# 153-06A_Mode_X_with_status_LEDs.net
KiCad netlist of a schematic drawn in EAGLE
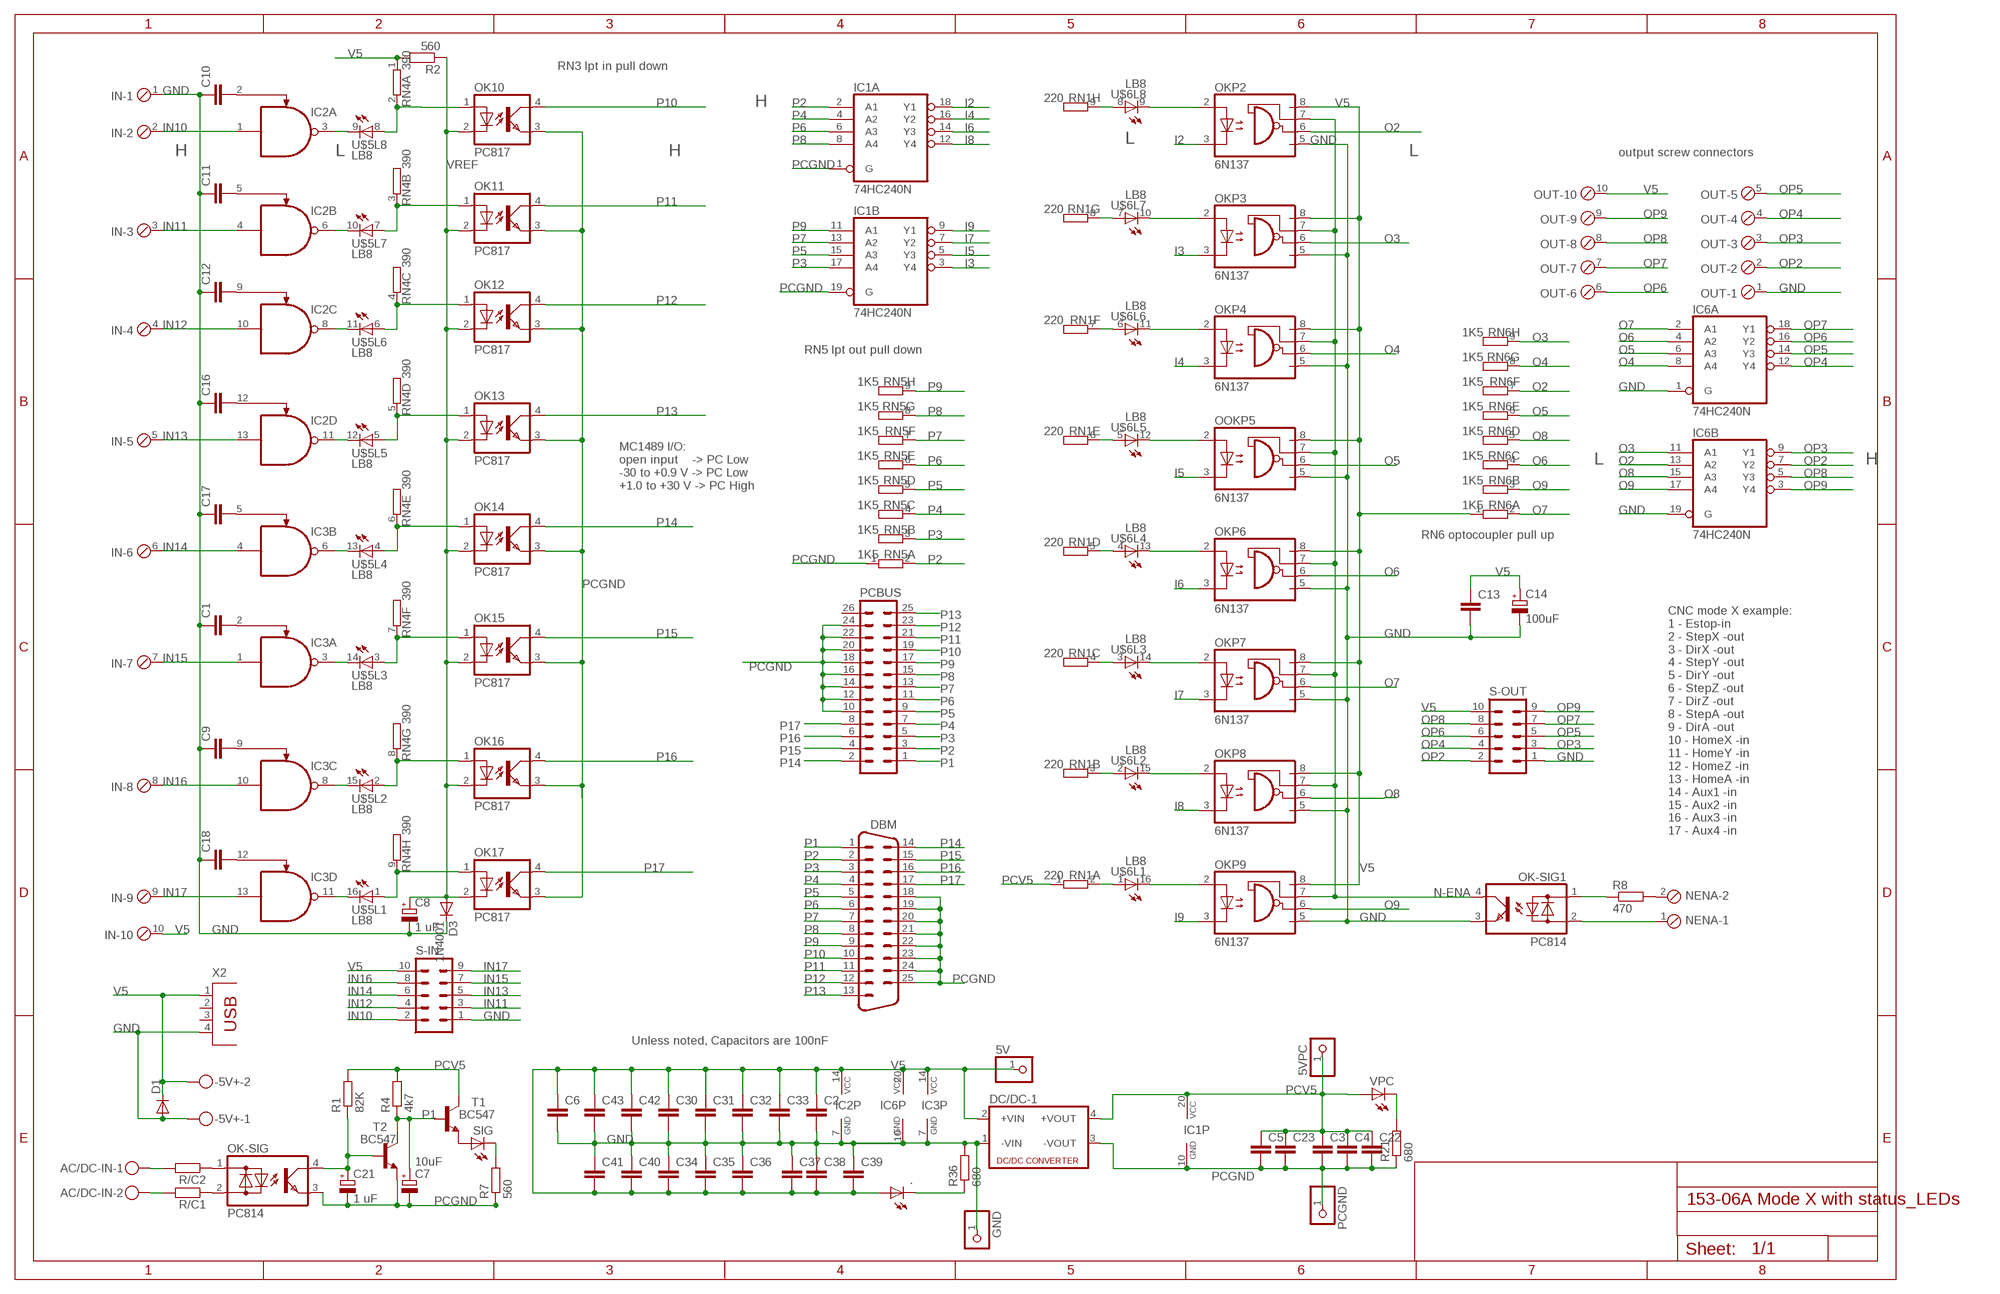
[diagram p0: schematic, sheet 1]

(export (version "E")
  (design (tool "Eeschema 10.0.6"))
  (components
    (comp (ref "-5V+")
      (value "MKDSN1,5/2-5,08")
      (footprint "eagle-import:MKDSN1,5_2-5,08")
      (libsource (lib "eagle-import") (part "MKDSN1,5/2-5,08"))
    )
    (comp (ref ".")
      (value "LED3MM")
      (footprint "eagle-import:LED3MM")
      (libsource (lib "eagle-import") (part "LED3MM"))
    )
    (comp (ref "5V")
      (value "PINHD-1X1")
      (footprint "eagle-import:1X01")
      (libsource (lib "eagle-import") (part "PINHD-1X1"))
    )
    (comp (ref "5VPC")
      (value "PINHD-1X1")
      (footprint "eagle-import:1X01")
      (libsource (lib "eagle-import") (part "PINHD-1X1"))
    )
    (comp (ref "AC/DC-IN")
      (value "MKDSN1,5/2-5,08")
      (footprint "eagle-import:MKDSN1,5_2-5,08")
      (libsource (lib "eagle-import") (part "MKDSN1,5/2-5,08"))
    )
    (comp (ref "C1")
      (value "C-EU025-024X044")
      (footprint "eagle-import:C025-024X044")
      (libsource (lib "eagle-import") (part "C-EU025-024X044"))
    )
    (comp (ref "C2")
      (value "C-EU025-024X044")
      (footprint "eagle-import:C025-024X044")
      (libsource (lib "eagle-import") (part "C-EU025-024X044"))
    )
    (comp (ref "C3")
      (value "C-EU025-024X044")
      (footprint "eagle-import:C025-024X044")
      (libsource (lib "eagle-import") (part "C-EU025-024X044"))
    )
    (comp (ref "C4")
      (value "C-EU025-024X044")
      (footprint "eagle-import:C025-024X044")
      (libsource (lib "eagle-import") (part "C-EU025-024X044"))
    )
    (comp (ref "C5")
      (value "C-EU025-024X044")
      (footprint "eagle-import:C025-024X044")
      (libsource (lib "eagle-import") (part "C-EU025-024X044"))
    )
    (comp (ref "C6")
      (value "C-EU025-024X044")
      (footprint "eagle-import:C025-024X044")
      (libsource (lib "eagle-import") (part "C-EU025-024X044"))
    )
    (comp (ref "C7")
      (value "10uF")
      (footprint "eagle-import:E5-6")
      (libsource (lib "eagle-import") (part "CPOL-EUE5-6"))
    )
    (comp (ref "C8")
      (value "1 uF")
      (footprint "eagle-import:E2,5-6")
      (libsource (lib "eagle-import") (part "CPOL-EUE2.5-6"))
    )
    (comp (ref "C9")
      (value "C-EU025-024X044")
      (footprint "eagle-import:C025-024X044")
      (libsource (lib "eagle-import") (part "C-EU025-024X044"))
    )
    (comp (ref "C10")
      (value "C-EU025-024X044")
      (footprint "eagle-import:C025-024X044")
      (libsource (lib "eagle-import") (part "C-EU025-024X044"))
    )
    (comp (ref "C11")
      (value "C-EU025-024X044")
      (footprint "eagle-import:C025-024X044")
      (libsource (lib "eagle-import") (part "C-EU025-024X044"))
    )
    (comp (ref "C12")
      (value "C-EU025-024X044")
      (footprint "eagle-import:C025-024X044")
      (libsource (lib "eagle-import") (part "C-EU025-024X044"))
    )
    (comp (ref "C13")
      (value "C-EU025-024X044")
      (footprint "eagle-import:C025-024X044")
      (libsource (lib "eagle-import") (part "C-EU025-024X044"))
    )
    (comp (ref "C14")
      (value "100uF")
      (footprint "eagle-import:E3,5-8")
      (libsource (lib "eagle-import") (part "CPOL-EUE3.5-8"))
    )
    (comp (ref "C16")
      (value "C-EU025-024X044")
      (footprint "eagle-import:C025-024X044")
      (libsource (lib "eagle-import") (part "C-EU025-024X044"))
    )
    (comp (ref "C17")
      (value "C-EU025-024X044")
      (footprint "eagle-import:C025-024X044")
      (libsource (lib "eagle-import") (part "C-EU025-024X044"))
    )
    (comp (ref "C18")
      (value "C-EU025-024X044")
      (footprint "eagle-import:C025-024X044")
      (libsource (lib "eagle-import") (part "C-EU025-024X044"))
    )
    (comp (ref "C21")
      (value "1 uF")
      (footprint "eagle-import:E2,5-6")
      (libsource (lib "eagle-import") (part "CPOL-EUE2.5-6"))
    )
    (comp (ref "C22")
      (value "C-EU025-024X044")
      (footprint "eagle-import:C025-024X044")
      (libsource (lib "eagle-import") (part "C-EU025-024X044"))
    )
    (comp (ref "C23")
      (value "C-EU025-024X044")
      (footprint "eagle-import:C025-024X044")
      (libsource (lib "eagle-import") (part "C-EU025-024X044"))
    )
    (comp (ref "C30")
      (value "C-EU025-024X044")
      (footprint "eagle-import:C025-024X044")
      (libsource (lib "eagle-import") (part "C-EU025-024X044"))
    )
    (comp (ref "C31")
      (value "C-EU025-024X044")
      (footprint "eagle-import:C025-024X044")
      (libsource (lib "eagle-import") (part "C-EU025-024X044"))
    )
    (comp (ref "C32")
      (value "C-EU025-024X044")
      (footprint "eagle-import:C025-024X044")
      (libsource (lib "eagle-import") (part "C-EU025-024X044"))
    )
    (comp (ref "C33")
      (value "C-EU025-024X044")
      (footprint "eagle-import:C025-024X044")
      (libsource (lib "eagle-import") (part "C-EU025-024X044"))
    )
    (comp (ref "C34")
      (value "C-EU025-024X044")
      (footprint "eagle-import:C025-024X044")
      (libsource (lib "eagle-import") (part "C-EU025-024X044"))
    )
    (comp (ref "C35")
      (value "C-EU025-024X044")
      (footprint "eagle-import:C025-024X044")
      (libsource (lib "eagle-import") (part "C-EU025-024X044"))
    )
    (comp (ref "C36")
      (value "C-EU025-024X044")
      (footprint "eagle-import:C025-024X044")
      (libsource (lib "eagle-import") (part "C-EU025-024X044"))
    )
    (comp (ref "C37")
      (value "C-EU025-024X044")
      (footprint "eagle-import:C025-024X044")
      (libsource (lib "eagle-import") (part "C-EU025-024X044"))
    )
    (comp (ref "C38")
      (value "C-EU025-024X044")
      (footprint "eagle-import:C025-024X044")
      (libsource (lib "eagle-import") (part "C-EU025-024X044"))
    )
    (comp (ref "C39")
      (value "C-EU025-024X044")
      (footprint "eagle-import:C025-024X044")
      (libsource (lib "eagle-import") (part "C-EU025-024X044"))
    )
    (comp (ref "C40")
      (value "C-EU025-024X044")
      (footprint "eagle-import:C025-024X044")
      (libsource (lib "eagle-import") (part "C-EU025-024X044"))
    )
    (comp (ref "C41")
      (value "C-EU025-024X044")
      (footprint "eagle-import:C025-024X044")
      (libsource (lib "eagle-import") (part "C-EU025-024X044"))
    )
    (comp (ref "C42")
      (value "C-EU025-024X044")
      (footprint "eagle-import:C025-024X044")
      (libsource (lib "eagle-import") (part "C-EU025-024X044"))
    )
    (comp (ref "C43")
      (value "C-EU025-024X044")
      (footprint "eagle-import:C025-024X044")
      (libsource (lib "eagle-import") (part "C-EU025-024X044"))
    )
    (comp (ref "D1")
      (value "1N4148DO35-10")
      (footprint "eagle-import:DO35-10")
      (libsource (lib "eagle-import") (part "1N4148DO35-10"))
    )
    (comp (ref "D3")
      (value "1N4001")
      (footprint "eagle-import:DO35-10")
      (libsource (lib "eagle-import") (part "1N4148DO35-10"))
    )
    (comp (ref "DBM")
      (value "M25HP")
      (footprint "eagle-import:M25HP")
      (libsource (lib "eagle-import") (part "M25HP"))
    )
    (comp (ref "DC/DC-1")
      (value "VA-1205S")
      (footprint "eagle-import:4SIL")
      (libsource (lib "eagle-import") (part "VA-?S1205"))
    )
    (comp (ref "GND")
      (value "PINHD-1X1")
      (footprint "eagle-import:1X01")
      (libsource (lib "eagle-import") (part "PINHD-1X1"))
    )
    (comp (ref "IC1")
      (value "74HC240N")
      (footprint "eagle-import:DIL20")
      (libsource (lib "eagle-import") (part "74240NHC"))
    )
    (comp (ref "IC2")
      (value "MC1489DIP")
      (footprint "eagle-import:DIL14")
      (libsource (lib "eagle-import") (part "MC1489DIP"))
    )
    (comp (ref "IC3")
      (value "MC1489DIP")
      (footprint "eagle-import:DIL14")
      (libsource (lib "eagle-import") (part "MC1489DIP"))
    )
    (comp (ref "IC6")
      (value "74HC240N")
      (footprint "eagle-import:DIL20")
      (libsource (lib "eagle-import") (part "74240NHC"))
    )
    (comp (ref "IN")
      (value "MPT10")
      (footprint "eagle-import:10POL254")
      (libsource (lib "eagle-import") (part "MPT10"))
    )
    (comp (ref "NENA")
      (value "MPT2")
      (footprint "eagle-import:2POL254")
      (libsource (lib "eagle-import") (part "MPT2"))
    )
    (comp (ref "OK-SIG")
      (value "PC814")
      (footprint "eagle-import:DIL04")
      (libsource (lib "eagle-import") (part "PC814"))
    )
    (comp (ref "OK-SIG1")
      (value "PC814")
      (footprint "eagle-import:DIL04")
      (libsource (lib "eagle-import") (part "PC814"))
    )
    (comp (ref "OK10")
      (value "PC817")
      (footprint "eagle-import:DIL04")
      (fields (field (name "MPN") "PC817X4J000F"))
      (libsource (lib "eagle-import") (part "PC817"))
    )
    (comp (ref "OK11")
      (value "PC817")
      (footprint "eagle-import:DIL04")
      (fields (field (name "MPN") "PC817X4J000F"))
      (libsource (lib "eagle-import") (part "PC817"))
    )
    (comp (ref "OK12")
      (value "PC817")
      (footprint "eagle-import:DIL04")
      (fields (field (name "MPN") "PC817X4J000F"))
      (libsource (lib "eagle-import") (part "PC817"))
    )
    (comp (ref "OK13")
      (value "PC817")
      (footprint "eagle-import:DIL04")
      (fields (field (name "MPN") "PC817X4J000F"))
      (libsource (lib "eagle-import") (part "PC817"))
    )
    (comp (ref "OK14")
      (value "PC817")
      (footprint "eagle-import:DIL04")
      (fields (field (name "MPN") "PC817X4J000F"))
      (libsource (lib "eagle-import") (part "PC817"))
    )
    (comp (ref "OK15")
      (value "PC817")
      (footprint "eagle-import:DIL04")
      (fields (field (name "MPN") "PC817X4J000F"))
      (libsource (lib "eagle-import") (part "PC817"))
    )
    (comp (ref "OK16")
      (value "PC817")
      (footprint "eagle-import:DIL04")
      (fields (field (name "MPN") "PC817X4J000F"))
      (libsource (lib "eagle-import") (part "PC817"))
    )
    (comp (ref "OK17")
      (value "PC817")
      (footprint "eagle-import:DIL04")
      (fields (field (name "MPN") "PC817X4J000F"))
      (libsource (lib "eagle-import") (part "PC817"))
    )
    (comp (ref "OKP2")
      (value "6N137")
      (footprint "eagle-import:DIL08")
      (libsource (lib "eagle-import") (part "6N137"))
    )
    (comp (ref "OKP3")
      (value "6N137")
      (footprint "eagle-import:DIL08")
      (libsource (lib "eagle-import") (part "6N137"))
    )
    (comp (ref "OKP4")
      (value "6N137")
      (footprint "eagle-import:DIL08")
      (libsource (lib "eagle-import") (part "6N137"))
    )
    (comp (ref "OKP6")
      (value "6N137")
      (footprint "eagle-import:DIL08")
      (libsource (lib "eagle-import") (part "6N137"))
    )
    (comp (ref "OKP7")
      (value "6N137")
      (footprint "eagle-import:DIL08")
      (libsource (lib "eagle-import") (part "6N137"))
    )
    (comp (ref "OKP8")
      (value "6N137")
      (footprint "eagle-import:DIL08")
      (libsource (lib "eagle-import") (part "6N137"))
    )
    (comp (ref "OKP9")
      (value "6N137")
      (footprint "eagle-import:DIL08")
      (libsource (lib "eagle-import") (part "6N137"))
    )
    (comp (ref "OOKP5")
      (value "6N137")
      (footprint "eagle-import:DIL08")
      (libsource (lib "eagle-import") (part "6N137"))
    )
    (comp (ref "OUT")
      (value "MPT10")
      (footprint "eagle-import:10POL254")
      (libsource (lib "eagle-import") (part "MPT10"))
    )
    (comp (ref "PCBUS")
      (value "ML26")
      (footprint "eagle-import:ML26")
      (libsource (lib "eagle-import") (part "ML26"))
    )
    (comp (ref "PCGND")
      (value "PINHD-1X1")
      (footprint "eagle-import:1X01")
      (libsource (lib "eagle-import") (part "PINHD-1X1"))
    )
    (comp (ref "R/C1")
      (value "R-EU_0309/10")
      (footprint "eagle-import:0309_10")
      (libsource (lib "eagle-import") (part "R-EU_0309/10"))
    )
    (comp (ref "R/C2")
      (value "R-EU_0309/10")
      (footprint "eagle-import:0309_10")
      (libsource (lib "eagle-import") (part "R-EU_0309/10"))
    )
    (comp (ref "R1")
      (value "82K")
      (footprint "eagle-import:0207_10")
      (libsource (lib "eagle-import") (part "R-EU_0207/10"))
    )
    (comp (ref "R2")
      (value "560")
      (footprint "eagle-import:0207_10")
      (libsource (lib "eagle-import") (part "R-EU_0207/10"))
    )
    (comp (ref "R4")
      (value "4k7")
      (footprint "eagle-import:0207_10")
      (libsource (lib "eagle-import") (part "R-EU_0207/10"))
    )
    (comp (ref "R7")
      (value "560")
      (footprint "eagle-import:0207_10")
      (libsource (lib "eagle-import") (part "R-EU_0207/10"))
    )
    (comp (ref "R8")
      (value "470")
      (footprint "eagle-import:0207_10")
      (libsource (lib "eagle-import") (part "R-EU_0207/10"))
    )
    (comp (ref "R21")
      (value "680")
      (footprint "eagle-import:0207_10")
      (libsource (lib "eagle-import") (part "R-EU_0207/10"))
    )
    (comp (ref "R36")
      (value "680")
      (footprint "eagle-import:0207_10")
      (libsource (lib "eagle-import") (part "R-EU_0207/10"))
    )
    (comp (ref "RN1")
      (value "220")
      (footprint "eagle-import:SIL9")
      (libsource (lib "eagle-import") (part "GE08R"))
    )
    (comp (ref "RN4")
      (value "390")
      (footprint "eagle-import:SIL9")
      (libsource (lib "eagle-import") (part "GE08R"))
    )
    (comp (ref "RN5")
      (value "1K5")
      (footprint "eagle-import:SIL9")
      (libsource (lib "eagle-import") (part "GE08R"))
    )
    (comp (ref "RN6")
      (value "1K5")
      (footprint "eagle-import:SIL9")
      (libsource (lib "eagle-import") (part "GE08R"))
    )
    (comp (ref "S-IN")
      (value "ML10")
      (footprint "eagle-import:ML10")
      (libsource (lib "eagle-import") (part "ML10"))
    )
    (comp (ref "S-OUT")
      (value "ML10")
      (footprint "eagle-import:ML10")
      (libsource (lib "eagle-import") (part "ML10"))
    )
    (comp (ref "SIG")
      (value "LED3MM")
      (footprint "eagle-import:LED3MM")
      (libsource (lib "eagle-import") (part "LED3MM"))
    )
    (comp (ref "T1")
      (value "BC547")
      (footprint "eagle-import:TO92")
      (libsource (lib "eagle-import") (part "BC547"))
    )
    (comp (ref "T2")
      (value "BC547")
      (footprint "eagle-import:TO92")
      (libsource (lib "eagle-import") (part "BC547"))
    )
    (comp (ref "U$5")
      (value "LB8")
      (footprint "eagle-import:LB8")
      (libsource (lib "eagle-import") (part "LB8"))
    )
    (comp (ref "U$6")
      (value "LB8")
      (footprint "eagle-import:LB8")
      (libsource (lib "eagle-import") (part "LB8"))
    )
    (comp (ref "VPC")
      (value "LED3MM")
      (footprint "eagle-import:LED3MM")
      (libsource (lib "eagle-import") (part "LED3MM"))
    )
    (comp (ref "X2")
      (value "PN87520")
      (footprint "eagle-import:PN87520")
      (libsource (lib "eagle-import") (part "PN87520"))
    )
  )
  (nets
    (net (code "1") (name "/GND") (class "Default")
      (node (ref "-5V+") (pin "1") (pinfunction "KL_1") (pintype "passive"))
      (node (ref "C1") (pin "1") (pinfunction "1_1") (pintype "passive"))
      (node (ref "C10") (pin "1") (pinfunction "1_1") (pintype "passive"))
      (node (ref "C11") (pin "1") (pinfunction "1_1") (pintype "passive"))
      (node (ref "C12") (pin "1") (pinfunction "1_1") (pintype "passive"))
      (node (ref "C13") (pin "2") (pinfunction "2_2") (pintype "passive"))
      (node (ref "C14") (pin "-") (pinfunction "-_-") (pintype "passive"))
      (node (ref "C16") (pin "1") (pinfunction "1_1") (pintype "passive"))
      (node (ref "C17") (pin "1") (pinfunction "1_1") (pintype "passive"))
      (node (ref "C18") (pin "1") (pinfunction "1_1") (pintype "passive"))
      (node (ref "C2") (pin "2") (pinfunction "2_2") (pintype "passive"))
      (node (ref "C30") (pin "2") (pinfunction "2_2") (pintype "passive"))
      (node (ref "C31") (pin "2") (pinfunction "2_2") (pintype "passive"))
      (node (ref "C32") (pin "2") (pinfunction "2_2") (pintype "passive"))
      (node (ref "C33") (pin "2") (pinfunction "2_2") (pintype "passive"))
      (node (ref "C34") (pin "1") (pinfunction "1_1") (pintype "passive"))
      (node (ref "C35") (pin "1") (pinfunction "1_1") (pintype "passive"))
      (node (ref "C36") (pin "1") (pinfunction "1_1") (pintype "passive"))
      (node (ref "C37") (pin "1") (pinfunction "1_1") (pintype "passive"))
      (node (ref "C38") (pin "1") (pinfunction "1_1") (pintype "passive"))
      (node (ref "C39") (pin "1") (pinfunction "1_1") (pintype "passive"))
      (node (ref "C40") (pin "1") (pinfunction "1_1") (pintype "passive"))
      (node (ref "C41") (pin "1") (pinfunction "1_1") (pintype "passive"))
      (node (ref "C42") (pin "2") (pinfunction "2_2") (pintype "passive"))
      (node (ref "C43") (pin "2") (pinfunction "2_2") (pintype "passive"))
      (node (ref "C6") (pin "2") (pinfunction "2_2") (pintype "passive"))
      (node (ref "C8") (pin "-") (pinfunction "-_-") (pintype "passive"))
      (node (ref "C9") (pin "1") (pinfunction "1_1") (pintype "passive"))
      (node (ref "D1") (pin "A") (pinfunction "A_A") (pintype "passive"))
      (node (ref "D3") (pin "C") (pinfunction "C_C") (pintype "passive"))
      (node (ref "DC/DC-1") (pin "1") (pinfunction "-VIN_1") (pintype "passive"))
      (node (ref "GND") (pin "1") (pinfunction "1_1") (pintype "passive"))
      (node (ref "IC2") (pin "7") (pinfunction "GND_7") (pintype "power_in"))
      (node (ref "IC3") (pin "7") (pinfunction "GND_7") (pintype "power_in"))
      (node (ref "IC6") (pin "1") (pinfunction "G_1") (pintype "input"))
      (node (ref "IC6") (pin "10") (pinfunction "GND_10") (pintype "power_in"))
      (node (ref "IC6") (pin "19") (pinfunction "G_19") (pintype "input"))
      (node (ref "IN") (pin "1") (pinfunction "1_1") (pintype "passive"))
      (node (ref "OK-SIG1") (pin "3") (pinfunction "E_3") (pintype "passive"))
      (node (ref "OKP2") (pin "5") (pinfunction "GND_5") (pintype "passive"))
      (node (ref "OKP3") (pin "5") (pinfunction "GND_5") (pintype "passive"))
      (node (ref "OKP4") (pin "5") (pinfunction "GND_5") (pintype "passive"))
      (node (ref "OKP6") (pin "5") (pinfunction "GND_5") (pintype "passive"))
      (node (ref "OKP7") (pin "5") (pinfunction "GND_5") (pintype "passive"))
      (node (ref "OKP8") (pin "5") (pinfunction "GND_5") (pintype "passive"))
      (node (ref "OKP9") (pin "5") (pinfunction "GND_5") (pintype "passive"))
      (node (ref "OOKP5") (pin "5") (pinfunction "GND_5") (pintype "passive"))
      (node (ref "OUT") (pin "1") (pinfunction "1_1") (pintype "passive"))
      (node (ref "R36") (pin "2") (pinfunction "2_2") (pintype "passive"))
      (node (ref "S-IN") (pin "1") (pinfunction "1_1") (pintype "passive"))
      (node (ref "S-OUT") (pin "1") (pinfunction "1_1") (pintype "passive"))
      (node (ref "X2") (pin "4") (pinfunction "4_4") (pintype "passive"))
    )
    (net (code "2") (name "/I2") (class "Default")
      (node (ref "IC1") (pin "18") (pinfunction "Y1_18") (pintype "tri_state"))
      (node (ref "OKP2") (pin "3") (pinfunction "C_3") (pintype "passive"))
    )
    (net (code "3") (name "/I3") (class "Default")
      (node (ref "IC1") (pin "3") (pinfunction "Y4_3") (pintype "tri_state"))
      (node (ref "OKP3") (pin "3") (pinfunction "C_3") (pintype "passive"))
    )
    (net (code "4") (name "/I4") (class "Default")
      (node (ref "IC1") (pin "16") (pinfunction "Y2_16") (pintype "tri_state"))
      (node (ref "OKP4") (pin "3") (pinfunction "C_3") (pintype "passive"))
    )
    (net (code "5") (name "/I5") (class "Default")
      (node (ref "IC1") (pin "5") (pinfunction "Y3_5") (pintype "tri_state"))
      (node (ref "OOKP5") (pin "3") (pinfunction "C_3") (pintype "passive"))
    )
    (net (code "6") (name "/I6") (class "Default")
      (node (ref "IC1") (pin "14") (pinfunction "Y3_14") (pintype "tri_state"))
      (node (ref "OKP6") (pin "3") (pinfunction "C_3") (pintype "passive"))
    )
    (net (code "7") (name "/I7") (class "Default")
      (node (ref "IC1") (pin "7") (pinfunction "Y2_7") (pintype "tri_state"))
      (node (ref "OKP7") (pin "3") (pinfunction "C_3") (pintype "passive"))
    )
    (net (code "8") (name "/I8") (class "Default")
      (node (ref "IC1") (pin "12") (pinfunction "Y4_12") (pintype "tri_state"))
      (node (ref "OKP8") (pin "3") (pinfunction "C_3") (pintype "passive"))
    )
    (net (code "9") (name "/I9") (class "Default")
      (node (ref "IC1") (pin "9") (pinfunction "Y1_9") (pintype "tri_state"))
      (node (ref "OKP9") (pin "3") (pinfunction "C_3") (pintype "passive"))
    )
    (net (code "10") (name "/IN10") (class "Default")
      (node (ref "IC2") (pin "1") (pinfunction "I0_1") (pintype "input"))
      (node (ref "IN") (pin "2") (pinfunction "1_2") (pintype "passive"))
      (node (ref "S-IN") (pin "2") (pinfunction "2_2") (pintype "passive"))
    )
    (net (code "11") (name "/IN11") (class "Default")
      (node (ref "IC2") (pin "4") (pinfunction "I0_4") (pintype "input"))
      (node (ref "IN") (pin "3") (pinfunction "1_3") (pintype "passive"))
      (node (ref "S-IN") (pin "3") (pinfunction "3_3") (pintype "passive"))
    )
    (net (code "12") (name "/IN12") (class "Default")
      (node (ref "IC2") (pin "10") (pinfunction "I0_10") (pintype "input"))
      (node (ref "IN") (pin "4") (pinfunction "1_4") (pintype "passive"))
      (node (ref "S-IN") (pin "4") (pinfunction "4_4") (pintype "passive"))
    )
    (net (code "13") (name "/IN13") (class "Default")
      (node (ref "IC2") (pin "13") (pinfunction "I0_13") (pintype "input"))
      (node (ref "IN") (pin "5") (pinfunction "1_5") (pintype "passive"))
      (node (ref "S-IN") (pin "5") (pinfunction "5_5") (pintype "passive"))
    )
    (net (code "14") (name "/IN14") (class "Default")
      (node (ref "IC3") (pin "4") (pinfunction "I0_4") (pintype "input"))
      (node (ref "IN") (pin "6") (pinfunction "1_6") (pintype "passive"))
      (node (ref "S-IN") (pin "6") (pinfunction "6_6") (pintype "passive"))
    )
    (net (code "15") (name "/IN15") (class "Default")
      (node (ref "IC3") (pin "1") (pinfunction "I0_1") (pintype "input"))
      (node (ref "IN") (pin "7") (pinfunction "1_7") (pintype "passive"))
      (node (ref "S-IN") (pin "7") (pinfunction "7_7") (pintype "passive"))
    )
    (net (code "16") (name "/IN16") (class "Default")
      (node (ref "IC3") (pin "10") (pinfunction "I0_10") (pintype "input"))
      (node (ref "IN") (pin "8") (pinfunction "1_8") (pintype "passive"))
      (node (ref "S-IN") (pin "8") (pinfunction "8_8") (pintype "passive"))
    )
    (net (code "17") (name "/IN17") (class "Default")
      (node (ref "IC3") (pin "13") (pinfunction "I0_13") (pintype "input"))
      (node (ref "IN") (pin "9") (pinfunction "1_9") (pintype "passive"))
      (node (ref "S-IN") (pin "9") (pinfunction "9_9") (pintype "passive"))
    )
    (net (code "18") (name "/N-ENA") (class "Default")
      (node (ref "OK-SIG1") (pin "4") (pinfunction "C_4") (pintype "passive"))
      (node (ref "OKP2") (pin "7") (pinfunction "VE_7") (pintype "passive"))
      (node (ref "OKP3") (pin "7") (pinfunction "VE_7") (pintype "passive"))
      (node (ref "OKP4") (pin "7") (pinfunction "VE_7") (pintype "passive"))
      (node (ref "OKP6") (pin "7") (pinfunction "VE_7") (pintype "passive"))
      (node (ref "OKP7") (pin "7") (pinfunction "VE_7") (pintype "passive"))
      (node (ref "OKP8") (pin "7") (pinfunction "VE_7") (pintype "passive"))
      (node (ref "OKP9") (pin "7") (pinfunction "VE_7") (pintype "passive"))
      (node (ref "OOKP5") (pin "7") (pinfunction "VE_7") (pintype "passive"))
    )
    (net (code "19") (name "/O2") (class "Default")
      (node (ref "IC6") (pin "13") (pinfunction "A2_13") (pintype "input"))
      (node (ref "OKP2") (pin "6") (pinfunction "VO_6") (pintype "passive"))
      (node (ref "RN6") (pin "7") (pinfunction "2_7") (pintype "passive"))
    )
    (net (code "20") (name "/O3") (class "Default")
      (node (ref "IC6") (pin "11") (pinfunction "A1_11") (pintype "input"))
      (node (ref "OKP3") (pin "6") (pinfunction "VO_6") (pintype "passive"))
      (node (ref "RN6") (pin "9") (pinfunction "2_9") (pintype "passive"))
    )
    (net (code "21") (name "/O4") (class "Default")
      (node (ref "IC6") (pin "8") (pinfunction "A4_8") (pintype "input"))
      (node (ref "OKP4") (pin "6") (pinfunction "VO_6") (pintype "passive"))
      (node (ref "RN6") (pin "8") (pinfunction "2_8") (pintype "passive"))
    )
    (net (code "22") (name "/O5") (class "Default")
      (node (ref "IC6") (pin "6") (pinfunction "A3_6") (pintype "input"))
      (node (ref "OOKP5") (pin "6") (pinfunction "VO_6") (pintype "passive"))
      (node (ref "RN6") (pin "6") (pinfunction "2_6") (pintype "passive"))
    )
    (net (code "23") (name "/O6") (class "Default")
      (node (ref "IC6") (pin "4") (pinfunction "A2_4") (pintype "input"))
      (node (ref "OKP6") (pin "6") (pinfunction "VO_6") (pintype "passive"))
      (node (ref "RN6") (pin "4") (pinfunction "2_4") (pintype "passive"))
    )
    (net (code "24") (name "/O7") (class "Default")
      (node (ref "IC6") (pin "2") (pinfunction "A1_2") (pintype "input"))
      (node (ref "OKP7") (pin "6") (pinfunction "VO_6") (pintype "passive"))
      (node (ref "RN6") (pin "2") (pinfunction "2_2") (pintype "passive"))
    )
    (net (code "25") (name "/O8") (class "Default")
      (node (ref "IC6") (pin "15") (pinfunction "A3_15") (pintype "input"))
      (node (ref "OKP8") (pin "6") (pinfunction "VO_6") (pintype "passive"))
      (node (ref "RN6") (pin "5") (pinfunction "2_5") (pintype "passive"))
    )
    (net (code "26") (name "/O9") (class "Default")
      (node (ref "IC6") (pin "17") (pinfunction "A4_17") (pintype "input"))
      (node (ref "OKP9") (pin "6") (pinfunction "VO_6") (pintype "passive"))
      (node (ref "RN6") (pin "3") (pinfunction "2_3") (pintype "passive"))
    )
    (net (code "27") (name "/OP2") (class "Default")
      (node (ref "IC6") (pin "7") (pinfunction "Y2_7") (pintype "tri_state"))
      (node (ref "OUT") (pin "2") (pinfunction "1_2") (pintype "passive"))
      (node (ref "S-OUT") (pin "2") (pinfunction "2_2") (pintype "passive"))
    )
    (net (code "28") (name "/OP3") (class "Default")
      (node (ref "IC6") (pin "9") (pinfunction "Y1_9") (pintype "tri_state"))
      (node (ref "OUT") (pin "3") (pinfunction "1_3") (pintype "passive"))
      (node (ref "S-OUT") (pin "3") (pinfunction "3_3") (pintype "passive"))
    )
    (net (code "29") (name "/OP4") (class "Default")
      (node (ref "IC6") (pin "12") (pinfunction "Y4_12") (pintype "tri_state"))
      (node (ref "OUT") (pin "4") (pinfunction "1_4") (pintype "passive"))
      (node (ref "S-OUT") (pin "4") (pinfunction "4_4") (pintype "passive"))
    )
    (net (code "30") (name "/OP5") (class "Default")
      (node (ref "IC6") (pin "14") (pinfunction "Y3_14") (pintype "tri_state"))
      (node (ref "OUT") (pin "5") (pinfunction "1_5") (pintype "passive"))
      (node (ref "S-OUT") (pin "5") (pinfunction "5_5") (pintype "passive"))
    )
    (net (code "31") (name "/OP6") (class "Default")
      (node (ref "IC6") (pin "16") (pinfunction "Y2_16") (pintype "tri_state"))
      (node (ref "OUT") (pin "6") (pinfunction "1_6") (pintype "passive"))
      (node (ref "S-OUT") (pin "6") (pinfunction "6_6") (pintype "passive"))
    )
    (net (code "32") (name "/OP7") (class "Default")
      (node (ref "IC6") (pin "18") (pinfunction "Y1_18") (pintype "tri_state"))
      (node (ref "OUT") (pin "7") (pinfunction "1_7") (pintype "passive"))
      (node (ref "S-OUT") (pin "7") (pinfunction "7_7") (pintype "passive"))
    )
    (net (code "33") (name "/OP8") (class "Default")
      (node (ref "IC6") (pin "5") (pinfunction "Y3_5") (pintype "tri_state"))
      (node (ref "OUT") (pin "8") (pinfunction "1_8") (pintype "passive"))
      (node (ref "S-OUT") (pin "8") (pinfunction "8_8") (pintype "passive"))
    )
    (net (code "34") (name "/OP9") (class "Default")
      (node (ref "IC6") (pin "3") (pinfunction "Y4_3") (pintype "tri_state"))
      (node (ref "OUT") (pin "9") (pinfunction "1_9") (pintype "passive"))
      (node (ref "S-OUT") (pin "9") (pinfunction "9_9") (pintype "passive"))
    )
    (net (code "35") (name "/P1") (class "Default")
      (node (ref "C7") (pin "+") (pinfunction "+_+") (pintype "passive"))
      (node (ref "DBM") (pin "1") (pinfunction "1_1") (pintype "passive"))
      (node (ref "PCBUS") (pin "1") (pinfunction "1_1") (pintype "passive"))
      (node (ref "R4") (pin "1") (pinfunction "1_1") (pintype "passive"))
      (node (ref "T1") (pin "2") (pinfunction "B_2") (pintype "passive"))
      (node (ref "T2") (pin "3") (pinfunction "C_3") (pintype "passive"))
    )
    (net (code "36") (name "/P2") (class "Default")
      (node (ref "DBM") (pin "2") (pinfunction "2_2") (pintype "passive"))
      (node (ref "IC1") (pin "2") (pinfunction "A1_2") (pintype "input"))
      (node (ref "PCBUS") (pin "3") (pinfunction "3_3") (pintype "passive"))
      (node (ref "RN5") (pin "2") (pinfunction "2_2") (pintype "passive"))
    )
    (net (code "37") (name "/P3") (class "Default")
      (node (ref "DBM") (pin "3") (pinfunction "3_3") (pintype "passive"))
      (node (ref "IC1") (pin "17") (pinfunction "A4_17") (pintype "input"))
      (node (ref "PCBUS") (pin "5") (pinfunction "5_5") (pintype "passive"))
      (node (ref "RN5") (pin "3") (pinfunction "2_3") (pintype "passive"))
    )
    (net (code "38") (name "/P4") (class "Default")
      (node (ref "DBM") (pin "4") (pinfunction "4_4") (pintype "passive"))
      (node (ref "IC1") (pin "4") (pinfunction "A2_4") (pintype "input"))
      (node (ref "PCBUS") (pin "7") (pinfunction "7_7") (pintype "passive"))
      (node (ref "RN5") (pin "4") (pinfunction "2_4") (pintype "passive"))
    )
    (net (code "39") (name "/P5") (class "Default")
      (node (ref "DBM") (pin "5") (pinfunction "5_5") (pintype "passive"))
      (node (ref "IC1") (pin "15") (pinfunction "A3_15") (pintype "input"))
      (node (ref "PCBUS") (pin "9") (pinfunction "9_9") (pintype "passive"))
      (node (ref "RN5") (pin "5") (pinfunction "2_5") (pintype "passive"))
    )
    (net (code "40") (name "/P6") (class "Default")
      (node (ref "DBM") (pin "6") (pinfunction "6_6") (pintype "passive"))
      (node (ref "IC1") (pin "6") (pinfunction "A3_6") (pintype "input"))
      (node (ref "PCBUS") (pin "11") (pinfunction "11_11") (pintype "passive"))
      (node (ref "RN5") (pin "6") (pinfunction "2_6") (pintype "passive"))
    )
    (net (code "41") (name "/P7") (class "Default")
      (node (ref "DBM") (pin "7") (pinfunction "7_7") (pintype "passive"))
      (node (ref "IC1") (pin "13") (pinfunction "A2_13") (pintype "input"))
      (node (ref "PCBUS") (pin "13") (pinfunction "13_13") (pintype "passive"))
      (node (ref "RN5") (pin "7") (pinfunction "2_7") (pintype "passive"))
    )
    (net (code "42") (name "/P8") (class "Default")
      (node (ref "DBM") (pin "8") (pinfunction "8_8") (pintype "passive"))
      (node (ref "IC1") (pin "8") (pinfunction "A4_8") (pintype "input"))
      (node (ref "PCBUS") (pin "15") (pinfunction "15_15") (pintype "passive"))
      (node (ref "RN5") (pin "8") (pinfunction "2_8") (pintype "passive"))
    )
    (net (code "43") (name "/P9") (class "Default")
      (node (ref "DBM") (pin "9") (pinfunction "9_9") (pintype "passive"))
      (node (ref "IC1") (pin "11") (pinfunction "A1_11") (pintype "input"))
      (node (ref "PCBUS") (pin "17") (pinfunction "17_17") (pintype "passive"))
      (node (ref "RN5") (pin "9") (pinfunction "2_9") (pintype "passive"))
    )
    (net (code "44") (name "/P10") (class "Default")
      (node (ref "DBM") (pin "10") (pinfunction "10_10") (pintype "passive"))
      (node (ref "OK10") (pin "4") (pinfunction "COL_4") (pintype "passive"))
      (node (ref "PCBUS") (pin "19") (pinfunction "19_19") (pintype "passive"))
    )
    (net (code "45") (name "/P11") (class "Default")
      (node (ref "DBM") (pin "11") (pinfunction "11_11") (pintype "passive"))
      (node (ref "OK11") (pin "4") (pinfunction "COL_4") (pintype "passive"))
      (node (ref "PCBUS") (pin "21") (pinfunction "21_21") (pintype "passive"))
    )
    (net (code "46") (name "/P12") (class "Default")
      (node (ref "DBM") (pin "12") (pinfunction "12_12") (pintype "passive"))
      (node (ref "OK12") (pin "4") (pinfunction "COL_4") (pintype "passive"))
      (node (ref "PCBUS") (pin "23") (pinfunction "23_23") (pintype "passive"))
    )
    (net (code "47") (name "/P13") (class "Default")
      (node (ref "DBM") (pin "13") (pinfunction "13_13") (pintype "passive"))
      (node (ref "OK13") (pin "4") (pinfunction "COL_4") (pintype "passive"))
      (node (ref "PCBUS") (pin "25") (pinfunction "25_25") (pintype "passive"))
    )
    (net (code "48") (name "/P14") (class "Default")
      (node (ref "DBM") (pin "14") (pinfunction "14_14") (pintype "passive"))
      (node (ref "OK14") (pin "4") (pinfunction "COL_4") (pintype "passive"))
      (node (ref "PCBUS") (pin "2") (pinfunction "2_2") (pintype "passive"))
    )
    (net (code "49") (name "/P15") (class "Default")
      (node (ref "DBM") (pin "15") (pinfunction "15_15") (pintype "passive"))
      (node (ref "OK15") (pin "4") (pinfunction "COL_4") (pintype "passive"))
      (node (ref "PCBUS") (pin "4") (pinfunction "4_4") (pintype "passive"))
    )
    (net (code "50") (name "/P16") (class "Default")
      (node (ref "DBM") (pin "16") (pinfunction "16_16") (pintype "passive"))
      (node (ref "OK16") (pin "4") (pinfunction "COL_4") (pintype "passive"))
      (node (ref "PCBUS") (pin "6") (pinfunction "6_6") (pintype "passive"))
    )
    (net (code "51") (name "/P17") (class "Default")
      (node (ref "DBM") (pin "17") (pinfunction "17_17") (pintype "passive"))
      (node (ref "OK17") (pin "4") (pinfunction "COL_4") (pintype "passive"))
      (node (ref "PCBUS") (pin "8") (pinfunction "8_8") (pintype "passive"))
    )
    (net (code "52") (name "/PCGND") (class "Default")
      (node (ref "C21") (pin "-") (pinfunction "-_-") (pintype "passive"))
      (node (ref "C22") (pin "2") (pinfunction "2_2") (pintype "passive"))
      (node (ref "C23") (pin "2") (pinfunction "2_2") (pintype "passive"))
      (node (ref "C3") (pin "2") (pinfunction "2_2") (pintype "passive"))
      (node (ref "C4") (pin "2") (pinfunction "2_2") (pintype "passive"))
      (node (ref "C5") (pin "2") (pinfunction "2_2") (pintype "passive"))
      (node (ref "C7") (pin "-") (pinfunction "-_-") (pintype "passive"))
      (node (ref "DBM") (pin "18") (pinfunction "18_18") (pintype "passive"))
      (node (ref "DBM") (pin "19") (pinfunction "19_19") (pintype "passive"))
      (node (ref "DBM") (pin "20") (pinfunction "20_20") (pintype "passive"))
      (node (ref "DBM") (pin "21") (pinfunction "21_21") (pintype "passive"))
      (node (ref "DBM") (pin "22") (pinfunction "22_22") (pintype "passive"))
      (node (ref "DBM") (pin "23") (pinfunction "23_23") (pintype "passive"))
      (node (ref "DBM") (pin "24") (pinfunction "24_24") (pintype "passive"))
      (node (ref "DBM") (pin "25") (pinfunction "25_25") (pintype "passive"))
      (node (ref "DC/DC-1") (pin "3") (pinfunction "-VOUT_3") (pintype "passive"))
      (node (ref "IC1") (pin "1") (pinfunction "G_1") (pintype "input"))
      (node (ref "IC1") (pin "10") (pinfunction "GND_10") (pintype "power_in"))
      (node (ref "IC1") (pin "19") (pinfunction "G_19") (pintype "input"))
      (node (ref "OK-SIG") (pin "3") (pinfunction "E_3") (pintype "passive"))
      (node (ref "OK10") (pin "3") (pinfunction "EMIT_3") (pintype "passive"))
      (node (ref "OK11") (pin "3") (pinfunction "EMIT_3") (pintype "passive"))
      (node (ref "OK12") (pin "3") (pinfunction "EMIT_3") (pintype "passive"))
      (node (ref "OK13") (pin "3") (pinfunction "EMIT_3") (pintype "passive"))
      (node (ref "OK14") (pin "3") (pinfunction "EMIT_3") (pintype "passive"))
      (node (ref "OK15") (pin "3") (pinfunction "EMIT_3") (pintype "passive"))
      (node (ref "OK16") (pin "3") (pinfunction "EMIT_3") (pintype "passive"))
      (node (ref "OK17") (pin "3") (pinfunction "EMIT_3") (pintype "passive"))
      (node (ref "PCBUS") (pin "10") (pinfunction "10_10") (pintype "passive"))
      (node (ref "PCBUS") (pin "12") (pinfunction "12_12") (pintype "passive"))
      (node (ref "PCBUS") (pin "14") (pinfunction "14_14") (pintype "passive"))
      (node (ref "PCBUS") (pin "16") (pinfunction "16_16") (pintype "passive"))
      (node (ref "PCBUS") (pin "18") (pinfunction "18_18") (pintype "passive"))
      (node (ref "PCBUS") (pin "20") (pinfunction "20_20") (pintype "passive"))
      (node (ref "PCBUS") (pin "22") (pinfunction "22_22") (pintype "passive"))
      (node (ref "PCBUS") (pin "24") (pinfunction "24_24") (pintype "passive"))
      (node (ref "PCGND") (pin "1") (pinfunction "1_1") (pintype "passive"))
      (node (ref "R21") (pin "1") (pinfunction "1_1") (pintype "passive"))
      (node (ref "R7") (pin "1") (pinfunction "1_1") (pintype "passive"))
      (node (ref "RN5") (pin "1") (pinfunction "1_1") (pintype "passive"))
      (node (ref "T2") (pin "1") (pinfunction "E_1") (pintype "passive"))
    )
    (net (code "53") (name "/PCV5") (class "Default")
      (node (ref "5VPC") (pin "1") (pinfunction "1_1") (pintype "passive"))
      (node (ref "C22") (pin "1") (pinfunction "1_1") (pintype "passive"))
      (node (ref "C23") (pin "1") (pinfunction "1_1") (pintype "passive"))
      (node (ref "C3") (pin "1") (pinfunction "1_1") (pintype "passive"))
      (node (ref "C4") (pin "1") (pinfunction "1_1") (pintype "passive"))
      (node (ref "C5") (pin "1") (pinfunction "1_1") (pintype "passive"))
      (node (ref "DC/DC-1") (pin "4") (pinfunction "+VOUT_4") (pintype "passive"))
      (node (ref "IC1") (pin "20") (pinfunction "VCC_20") (pintype "power_in"))
      (node (ref "R1") (pin "2") (pinfunction "2_2") (pintype "passive"))
      (node (ref "R4") (pin "2") (pinfunction "2_2") (pintype "passive"))
      (node (ref "RN1") (pin "1") (pinfunction "1_1") (pintype "passive"))
      (node (ref "T1") (pin "3") (pinfunction "C_3") (pintype "passive"))
      (node (ref "VPC") (pin "A") (pinfunction "A_A") (pintype "passive"))
    )
    (net (code "54") (name "/V5") (class "Default")
      (node (ref "-5V+") (pin "2") (pinfunction "KL_2") (pintype "passive"))
      (node (ref ".") (pin "A") (pinfunction "A_A") (pintype "passive"))
      (node (ref "5V") (pin "1") (pinfunction "1_1") (pintype "passive"))
      (node (ref "C13") (pin "1") (pinfunction "1_1") (pintype "passive"))
      (node (ref "C14") (pin "+") (pinfunction "+_+") (pintype "passive"))
      (node (ref "C2") (pin "1") (pinfunction "1_1") (pintype "passive"))
      (node (ref "C30") (pin "1") (pinfunction "1_1") (pintype "passive"))
      (node (ref "C31") (pin "1") (pinfunction "1_1") (pintype "passive"))
      (node (ref "C32") (pin "1") (pinfunction "1_1") (pintype "passive"))
      (node (ref "C33") (pin "1") (pinfunction "1_1") (pintype "passive"))
      (node (ref "C34") (pin "2") (pinfunction "2_2") (pintype "passive"))
      (node (ref "C35") (pin "2") (pinfunction "2_2") (pintype "passive"))
      (node (ref "C36") (pin "2") (pinfunction "2_2") (pintype "passive"))
      (node (ref "C37") (pin "2") (pinfunction "2_2") (pintype "passive"))
      (node (ref "C38") (pin "2") (pinfunction "2_2") (pintype "passive"))
      (node (ref "C39") (pin "2") (pinfunction "2_2") (pintype "passive"))
      (node (ref "C40") (pin "2") (pinfunction "2_2") (pintype "passive"))
      (node (ref "C41") (pin "2") (pinfunction "2_2") (pintype "passive"))
      (node (ref "C42") (pin "1") (pinfunction "1_1") (pintype "passive"))
      (node (ref "C43") (pin "1") (pinfunction "1_1") (pintype "passive"))
      (node (ref "C6") (pin "1") (pinfunction "1_1") (pintype "passive"))
      (node (ref "D1") (pin "C") (pinfunction "C_C") (pintype "passive"))
      (node (ref "DC/DC-1") (pin "2") (pinfunction "+VIN_2") (pintype "passive"))
      (node (ref "IC2") (pin "14") (pinfunction "VCC_14") (pintype "power_in"))
      (node (ref "IC3") (pin "14") (pinfunction "VCC_14") (pintype "power_in"))
      (node (ref "IC6") (pin "20") (pinfunction "VCC_20") (pintype "power_in"))
      (node (ref "IN") (pin "10") (pinfunction "1_10") (pintype "passive"))
      (node (ref "OKP2") (pin "8") (pinfunction "VCC_8") (pintype "passive"))
      (node (ref "OKP3") (pin "8") (pinfunction "VCC_8") (pintype "passive"))
      (node (ref "OKP4") (pin "8") (pinfunction "VCC_8") (pintype "passive"))
      (node (ref "OKP6") (pin "8") (pinfunction "VCC_8") (pintype "passive"))
      (node (ref "OKP7") (pin "8") (pinfunction "VCC_8") (pintype "passive"))
      (node (ref "OKP8") (pin "8") (pinfunction "VCC_8") (pintype "passive"))
      (node (ref "OKP9") (pin "8") (pinfunction "VCC_8") (pintype "passive"))
      (node (ref "OOKP5") (pin "8") (pinfunction "VCC_8") (pintype "passive"))
      (node (ref "OUT") (pin "10") (pinfunction "1_10") (pintype "passive"))
      (node (ref "R2") (pin "2") (pinfunction "2_2") (pintype "passive"))
      (node (ref "RN4") (pin "1") (pinfunction "1_1") (pintype "passive"))
      (node (ref "RN6") (pin "1") (pinfunction "1_1") (pintype "passive"))
      (node (ref "S-IN") (pin "10") (pinfunction "10_10") (pintype "passive"))
      (node (ref "S-OUT") (pin "10") (pinfunction "10_10") (pintype "passive"))
      (node (ref "X2") (pin "1") (pinfunction "1_1") (pintype "passive"))
    )
    (net (code "55") (name "/VREF") (class "Default")
      (node (ref "C8") (pin "+") (pinfunction "+_+") (pintype "passive"))
      (node (ref "D3") (pin "A") (pinfunction "A_A") (pintype "passive"))
      (node (ref "OK10") (pin "2") (pinfunction "C_2") (pintype "passive"))
      (node (ref "OK11") (pin "2") (pinfunction "C_2") (pintype "passive"))
      (node (ref "OK12") (pin "2") (pinfunction "C_2") (pintype "passive"))
      (node (ref "OK13") (pin "2") (pinfunction "C_2") (pintype "passive"))
      (node (ref "OK14") (pin "2") (pinfunction "C_2") (pintype "passive"))
      (node (ref "OK15") (pin "2") (pinfunction "C_2") (pintype "passive"))
      (node (ref "OK16") (pin "2") (pinfunction "C_2") (pintype "passive"))
      (node (ref "OK17") (pin "2") (pinfunction "C_2") (pintype "passive"))
      (node (ref "R2") (pin "1") (pinfunction "1_1") (pintype "passive"))
    )
    (net (code "56") (name "Net-(.-C)") (class "Default")
      (node (ref ".") (pin "K") (pinfunction "C_K") (pintype "passive"))
      (node (ref "R36") (pin "1") (pinfunction "1_1") (pintype "passive"))
    )
    (net (code "57") (name "Net-(AC/DC-INA-KL)") (class "Default")
      (node (ref "AC/DC-IN") (pin "1") (pinfunction "KL_1") (pintype "passive"))
      (node (ref "R/C2") (pin "2") (pinfunction "2_2") (pintype "passive"))
    )
    (net (code "58") (name "Net-(AC/DC-INB-KL)") (class "Default")
      (node (ref "AC/DC-IN") (pin "2") (pinfunction "KL_2") (pintype "passive"))
      (node (ref "R/C1") (pin "2") (pinfunction "2_2") (pintype "passive"))
    )
    (net (code "59") (name "Net-(IC2A-I1)") (class "Default")
      (node (ref "C10") (pin "2") (pinfunction "2_2") (pintype "passive"))
      (node (ref "IC2") (pin "2") (pinfunction "I1_2") (pintype "input"))
    )
    (net (code "60") (name "Net-(IC2A-O)") (class "Default")
      (node (ref "IC2") (pin "3") (pinfunction "O_3") (pintype "output"))
      (node (ref "U$5") (pin "9") (pinfunction "C_9") (pintype "passive"))
    )
    (net (code "61") (name "Net-(IC2B-I1)") (class "Default")
      (node (ref "C11") (pin "2") (pinfunction "2_2") (pintype "passive"))
      (node (ref "IC2") (pin "5") (pinfunction "I1_5") (pintype "input"))
    )
    (net (code "62") (name "Net-(IC2B-O)") (class "Default")
      (node (ref "IC2") (pin "6") (pinfunction "O_6") (pintype "output"))
      (node (ref "U$5") (pin "10") (pinfunction "C_10") (pintype "passive"))
    )
    (net (code "63") (name "Net-(IC2C-I1)") (class "Default")
      (node (ref "C12") (pin "2") (pinfunction "2_2") (pintype "passive"))
      (node (ref "IC2") (pin "9") (pinfunction "I1_9") (pintype "input"))
    )
    (net (code "64") (name "Net-(IC2C-O)") (class "Default")
      (node (ref "IC2") (pin "8") (pinfunction "O_8") (pintype "output"))
      (node (ref "U$5") (pin "11") (pinfunction "C_11") (pintype "passive"))
    )
    (net (code "65") (name "Net-(IC2D-I1)") (class "Default")
      (node (ref "C16") (pin "2") (pinfunction "2_2") (pintype "passive"))
      (node (ref "IC2") (pin "12") (pinfunction "I1_12") (pintype "input"))
    )
    (net (code "66") (name "Net-(IC2D-O)") (class "Default")
      (node (ref "IC2") (pin "11") (pinfunction "O_11") (pintype "output"))
      (node (ref "U$5") (pin "12") (pinfunction "C_12") (pintype "passive"))
    )
    (net (code "67") (name "Net-(IC3A-I1)") (class "Default")
      (node (ref "C1") (pin "2") (pinfunction "2_2") (pintype "passive"))
      (node (ref "IC3") (pin "2") (pinfunction "I1_2") (pintype "input"))
    )
    (net (code "68") (name "Net-(IC3A-O)") (class "Default")
      (node (ref "IC3") (pin "3") (pinfunction "O_3") (pintype "output"))
      (node (ref "U$5") (pin "14") (pinfunction "C_14") (pintype "passive"))
    )
    (net (code "69") (name "Net-(IC3B-I1)") (class "Default")
      (node (ref "C17") (pin "2") (pinfunction "2_2") (pintype "passive"))
      (node (ref "IC3") (pin "5") (pinfunction "I1_5") (pintype "input"))
    )
    (net (code "70") (name "Net-(IC3B-O)") (class "Default")
      (node (ref "IC3") (pin "6") (pinfunction "O_6") (pintype "output"))
      (node (ref "U$5") (pin "13") (pinfunction "C_13") (pintype "passive"))
    )
    (net (code "71") (name "Net-(IC3C-I1)") (class "Default")
      (node (ref "C9") (pin "2") (pinfunction "2_2") (pintype "passive"))
      (node (ref "IC3") (pin "9") (pinfunction "I1_9") (pintype "input"))
    )
    (net (code "72") (name "Net-(IC3C-O)") (class "Default")
      (node (ref "IC3") (pin "8") (pinfunction "O_8") (pintype "output"))
      (node (ref "U$5") (pin "15") (pinfunction "C_15") (pintype "passive"))
    )
    (net (code "73") (name "Net-(IC3D-I1)") (class "Default")
      (node (ref "C18") (pin "2") (pinfunction "2_2") (pintype "passive"))
      (node (ref "IC3") (pin "12") (pinfunction "I1_12") (pintype "input"))
    )
    (net (code "74") (name "Net-(IC3D-O)") (class "Default")
      (node (ref "IC3") (pin "11") (pinfunction "O_11") (pintype "output"))
      (node (ref "U$5") (pin "16") (pinfunction "C_16") (pintype "passive"))
    )
    (net (code "75") (name "Net-(NENAB-1)") (class "Default")
      (node (ref "NENA") (pin "2") (pinfunction "1_2") (pintype "passive"))
      (node (ref "R8") (pin "2") (pinfunction "2_2") (pintype "passive"))
    )
    (net (code "76") (name "Net-(OK-SIG-AC1)") (class "Default")
      (node (ref "OK-SIG") (pin "1") (pinfunction "AC1_1") (pintype "passive"))
      (node (ref "R/C2") (pin "1") (pinfunction "1_1") (pintype "passive"))
    )
    (net (code "77") (name "Net-(OK-SIG-AC2)") (class "Default")
      (node (ref "OK-SIG") (pin "2") (pinfunction "AC2_2") (pintype "passive"))
      (node (ref "R/C1") (pin "1") (pinfunction "1_1") (pintype "passive"))
    )
    (net (code "78") (name "Net-(OK-SIG-C)") (class "Default")
      (node (ref "C21") (pin "+") (pinfunction "+_+") (pintype "passive"))
      (node (ref "OK-SIG") (pin "4") (pinfunction "C_4") (pintype "passive"))
      (node (ref "R1") (pin "1") (pinfunction "1_1") (pintype "passive"))
      (node (ref "T2") (pin "2") (pinfunction "B_2") (pintype "passive"))
    )
    (net (code "79") (name "Net-(OK-SIG1-AC1)") (class "Default")
      (node (ref "OK-SIG1") (pin "1") (pinfunction "AC1_1") (pintype "passive"))
      (node (ref "R8") (pin "1") (pinfunction "1_1") (pintype "passive"))
    )
    (net (code "80") (name "Net-(OK-SIG1-AC2)") (class "Default")
      (node (ref "NENA") (pin "1") (pinfunction "1_1") (pintype "passive"))
      (node (ref "OK-SIG1") (pin "2") (pinfunction "AC2_2") (pintype "passive"))
    )
    (net (code "81") (name "Net-(OK10-A)") (class "Default")
      (node (ref "OK10") (pin "1") (pinfunction "A_1") (pintype "passive"))
      (node (ref "RN4") (pin "2") (pinfunction "2_2") (pintype "passive"))
      (node (ref "U$5") (pin "8") (pinfunction "A_8") (pintype "passive"))
    )
    (net (code "82") (name "Net-(OK11-A)") (class "Default")
      (node (ref "OK11") (pin "1") (pinfunction "A_1") (pintype "passive"))
      (node (ref "RN4") (pin "3") (pinfunction "2_3") (pintype "passive"))
      (node (ref "U$5") (pin "7") (pinfunction "A_7") (pintype "passive"))
    )
    (net (code "83") (name "Net-(OK12-A)") (class "Default")
      (node (ref "OK12") (pin "1") (pinfunction "A_1") (pintype "passive"))
      (node (ref "RN4") (pin "4") (pinfunction "2_4") (pintype "passive"))
      (node (ref "U$5") (pin "6") (pinfunction "A_6") (pintype "passive"))
    )
    (net (code "84") (name "Net-(OK13-A)") (class "Default")
      (node (ref "OK13") (pin "1") (pinfunction "A_1") (pintype "passive"))
      (node (ref "RN4") (pin "5") (pinfunction "2_5") (pintype "passive"))
      (node (ref "U$5") (pin "5") (pinfunction "A_5") (pintype "passive"))
    )
    (net (code "85") (name "Net-(OK14-A)") (class "Default")
      (node (ref "OK14") (pin "1") (pinfunction "A_1") (pintype "passive"))
      (node (ref "RN4") (pin "6") (pinfunction "2_6") (pintype "passive"))
      (node (ref "U$5") (pin "4") (pinfunction "A_4") (pintype "passive"))
    )
    (net (code "86") (name "Net-(OK15-A)") (class "Default")
      (node (ref "OK15") (pin "1") (pinfunction "A_1") (pintype "passive"))
      (node (ref "RN4") (pin "7") (pinfunction "2_7") (pintype "passive"))
      (node (ref "U$5") (pin "3") (pinfunction "A_3") (pintype "passive"))
    )
    (net (code "87") (name "Net-(OK16-A)") (class "Default")
      (node (ref "OK16") (pin "1") (pinfunction "A_1") (pintype "passive"))
      (node (ref "RN4") (pin "8") (pinfunction "2_8") (pintype "passive"))
      (node (ref "U$5") (pin "2") (pinfunction "A_2") (pintype "passive"))
    )
    (net (code "88") (name "Net-(OK17-A)") (class "Default")
      (node (ref "OK17") (pin "1") (pinfunction "A_1") (pintype "passive"))
      (node (ref "RN4") (pin "9") (pinfunction "2_9") (pintype "passive"))
      (node (ref "U$5") (pin "1") (pinfunction "A_1") (pintype "passive"))
    )
    (net (code "89") (name "Net-(OKP2-A)") (class "Default")
      (node (ref "OKP2") (pin "2") (pinfunction "A_2") (pintype "passive"))
      (node (ref "U$6") (pin "9") (pinfunction "C_9") (pintype "passive"))
    )
    (net (code "90") (name "Net-(OKP3-A)") (class "Default")
      (node (ref "OKP3") (pin "2") (pinfunction "A_2") (pintype "passive"))
      (node (ref "U$6") (pin "10") (pinfunction "C_10") (pintype "passive"))
    )
    (net (code "91") (name "Net-(OKP4-A)") (class "Default")
      (node (ref "OKP4") (pin "2") (pinfunction "A_2") (pintype "passive"))
      (node (ref "U$6") (pin "11") (pinfunction "C_11") (pintype "passive"))
    )
    (net (code "92") (name "Net-(OKP6-A)") (class "Default")
      (node (ref "OKP6") (pin "2") (pinfunction "A_2") (pintype "passive"))
      (node (ref "U$6") (pin "13") (pinfunction "C_13") (pintype "passive"))
    )
    (net (code "93") (name "Net-(OKP7-A)") (class "Default")
      (node (ref "OKP7") (pin "2") (pinfunction "A_2") (pintype "passive"))
      (node (ref "U$6") (pin "14") (pinfunction "C_14") (pintype "passive"))
    )
    (net (code "94") (name "Net-(OKP8-A)") (class "Default")
      (node (ref "OKP8") (pin "2") (pinfunction "A_2") (pintype "passive"))
      (node (ref "U$6") (pin "15") (pinfunction "C_15") (pintype "passive"))
    )
    (net (code "95") (name "Net-(OKP9-A)") (class "Default")
      (node (ref "OKP9") (pin "2") (pinfunction "A_2") (pintype "passive"))
      (node (ref "U$6") (pin "16") (pinfunction "C_16") (pintype "passive"))
    )
    (net (code "96") (name "Net-(OOKP5-A)") (class "Default")
      (node (ref "OOKP5") (pin "2") (pinfunction "A_2") (pintype "passive"))
      (node (ref "U$6") (pin "12") (pinfunction "C_12") (pintype "passive"))
    )
    (net (code "97") (name "Net-(RN1B-2)") (class "Default")
      (node (ref "RN1") (pin "3") (pinfunction "2_3") (pintype "passive"))
      (node (ref "U$6") (pin "2") (pinfunction "A_2") (pintype "passive"))
    )
    (net (code "98") (name "Net-(RN1C-2)") (class "Default")
      (node (ref "RN1") (pin "4") (pinfunction "2_4") (pintype "passive"))
      (node (ref "U$6") (pin "3") (pinfunction "A_3") (pintype "passive"))
    )
    (net (code "99") (name "Net-(RN1D-2)") (class "Default")
      (node (ref "RN1") (pin "5") (pinfunction "2_5") (pintype "passive"))
      (node (ref "U$6") (pin "4") (pinfunction "A_4") (pintype "passive"))
    )
    (net (code "100") (name "Net-(RN1E-2)") (class "Default")
      (node (ref "RN1") (pin "6") (pinfunction "2_6") (pintype "passive"))
      (node (ref "U$6") (pin "5") (pinfunction "A_5") (pintype "passive"))
    )
    (net (code "101") (name "Net-(RN1F-2)") (class "Default")
      (node (ref "RN1") (pin "7") (pinfunction "2_7") (pintype "passive"))
      (node (ref "U$6") (pin "6") (pinfunction "A_6") (pintype "passive"))
    )
    (net (code "102") (name "Net-(RN1G-2)") (class "Default")
      (node (ref "RN1") (pin "8") (pinfunction "2_8") (pintype "passive"))
      (node (ref "U$6") (pin "7") (pinfunction "A_7") (pintype "passive"))
    )
    (net (code "103") (name "Net-(RN1H-2)") (class "Default")
      (node (ref "RN1") (pin "9") (pinfunction "2_9") (pintype "passive"))
      (node (ref "U$6") (pin "8") (pinfunction "A_8") (pintype "passive"))
    )
    (net (code "104") (name "Net-(SIG-C)") (class "Default")
      (node (ref "R7") (pin "2") (pinfunction "2_2") (pintype "passive"))
      (node (ref "SIG") (pin "K") (pinfunction "C_K") (pintype "passive"))
    )
    (net (code "105") (name "Net-(T1-E)") (class "Default")
      (node (ref "SIG") (pin "A") (pinfunction "A_A") (pintype "passive"))
      (node (ref "T1") (pin "1") (pinfunction "E_1") (pintype "passive"))
    )
    (net (code "106") (name "Net-(U$6A-A)") (class "Default")
      (node (ref "RN1") (pin "2") (pinfunction "2_2") (pintype "passive"))
      (node (ref "U$6") (pin "1") (pinfunction "A_1") (pintype "passive"))
    )
    (net (code "107") (name "Net-(VPC-C)") (class "Default")
      (node (ref "R21") (pin "2") (pinfunction "2_2") (pintype "passive"))
      (node (ref "VPC") (pin "K") (pinfunction "C_K") (pintype "passive"))
    )
    (net (code "108") (name "unconnected-(PCBUS-Pad26)") (class "Default")
      (node (ref "PCBUS") (pin "26") (pinfunction "26_26") (pintype "passive"))
    )
    (net (code "109") (name "unconnected-(X2-Pad2)") (class "Default")
      (node (ref "X2") (pin "2") (pinfunction "2_2") (pintype "passive"))
    )
    (net (code "110") (name "unconnected-(X2-Pad3)") (class "Default")
      (node (ref "X2") (pin "3") (pinfunction "3_3") (pintype "passive"))
    )
  )
)
